# diskohedron4w_revc_termination.net
KiCad netlist of a schematic drawn in EAGLE
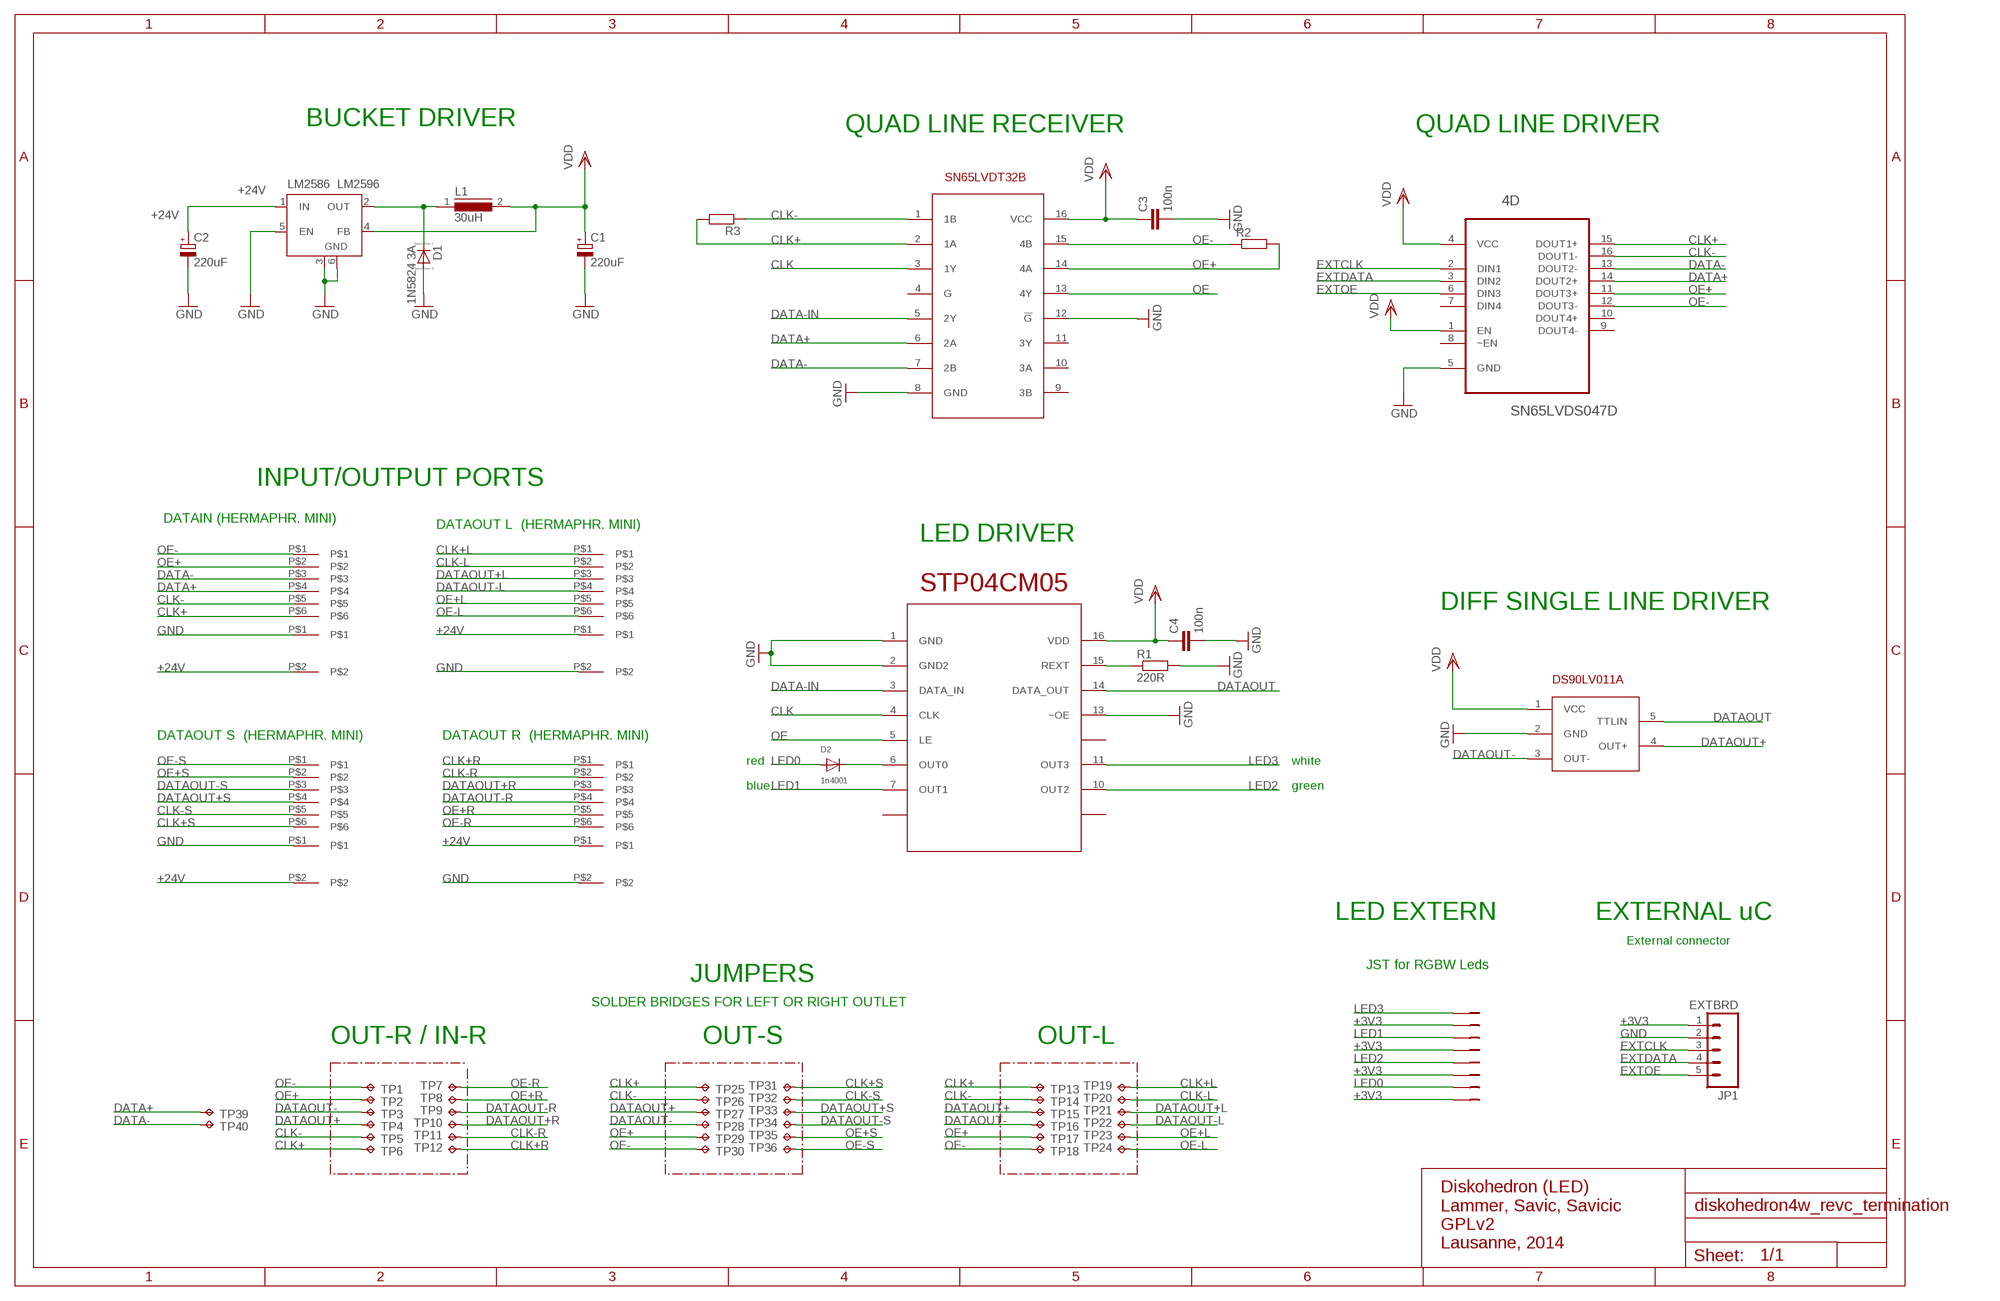
[diagram p0: schematic, sheet 1]

(export (version "E")
  (design (tool "Eeschema 10.0.6"))
  (components
    (comp (ref "1D")
      (value "DS90LV011A")
      (footprint "eagle-import:SOT23-5")
      (libsource (lib "eagle-import") (part "DS90LV011A"))
    )
    (comp (ref "4D")
      (value "SN65LVDS047D")
      (footprint "eagle-import:SOIC127P600X175-16N")
      (libsource (lib "eagle-import") (part "SN65LVDS047D"))
    )
    (comp (ref "4R")
      (value "SN65LVDST32")
      (footprint "eagle-import:SOIC16")
      (libsource (lib "eagle-import") (part "SN65LVDST32"))
    )
    (comp (ref "C1")
      (value "220uF")
      (footprint "eagle-import:175TMP-0810")
      (libsource (lib "eagle-import") (part "CPOL-EU175TMP-0810"))
    )
    (comp (ref "C2")
      (value "220uF")
      (footprint "eagle-import:175TMP-0810")
      (libsource (lib "eagle-import") (part "CPOL-EU175TMP-0810"))
    )
    (comp (ref "C3")
      (value "100n")
      (footprint "eagle-import:C0805")
      (libsource (lib "eagle-import") (part "C-EUC0805"))
    )
    (comp (ref "C4")
      (value "100n")
      (footprint "eagle-import:C0805")
      (libsource (lib "eagle-import") (part "C-EUC0805"))
    )
    (comp (ref "D1")
      (value "1N5824 3A")
      (footprint "eagle-import:DIODE_SMC")
      (libsource (lib "eagle-import") (part "DIODE_E-SMC"))
    )
    (comp (ref "D2")
      (value "1n4001")
      (footprint "eagle-import:SMADIODE")
      (libsource (lib "eagle-import") (part "DIODESMA"))
    )
    (comp (ref "IN1")
      (value "HERMAPHRODITMINI6PIN")
      (footprint "eagle-import:HERMAPHRODITMINI6PIN")
      (libsource (lib "eagle-import") (part "HERMAPHRODITMINI6PIN"))
    )
    (comp (ref "JP1")
      (value "EXTBRD")
      (footprint "eagle-import:1X05")
      (libsource (lib "eagle-import") (part "M05PTH"))
    )
    (comp (ref "JST")
      (value "8PIN-ZH")
      (footprint "eagle-import:B8B-ZH")
      (libsource (lib "eagle-import") (part "8PIN-ZH"))
    )
    (comp (ref "L1")
      (value "30uH")
      (footprint "eagle-import:DR127")
      (libsource (lib "eagle-import") (part "DR127"))
    )
    (comp (ref "LM2586")
      (value "LM2596")
      (footprint "eagle-import:TO263-5")
      (libsource (lib "eagle-import") (part "LM2596S"))
    )
    (comp (ref "OUT-L")
      (value "HERMAPHRODITMINI6PIN")
      (footprint "eagle-import:HERMAPHRODITMINI6PIN")
      (libsource (lib "eagle-import") (part "HERMAPHRODITMINI6PIN"))
    )
    (comp (ref "OUT-R")
      (value "HERMAPHRODITMINI6PIN")
      (footprint "eagle-import:HERMAPHRODITMINI6PIN")
      (libsource (lib "eagle-import") (part "HERMAPHRODITMINI6PIN"))
    )
    (comp (ref "OUT-R1")
      (value "HERMAPHRODITMINI6PIN")
      (footprint "eagle-import:HERMAPHRODITMINI6PIN")
      (libsource (lib "eagle-import") (part "HERMAPHRODITMINI6PIN"))
    )
    (comp (ref "R1")
      (value "220R")
      (footprint "eagle-import:M0805")
      (libsource (lib "eagle-import") (part "resistor_R-EU_M0805"))
    )
    (comp (ref "R2")
      (value "R-EU_R0402")
      (footprint "eagle-import:R0402")
      (libsource (lib "eagle-import") (part "R-EU_R0402"))
    )
    (comp (ref "R3")
      (value "R-EU_R0402")
      (footprint "eagle-import:R0402")
      (libsource (lib "eagle-import") (part "R-EU_R0402"))
    )
    (comp (ref "STP04")
      (value "STP04CM05")
      (footprint "eagle-import:TSSOP16")
      (libsource (lib "eagle-import") (part "STP04CM05"))
    )
    (comp (ref "TP1")
      (value "TPTP12SQ")
      (footprint "eagle-import:TP12SQ")
      (libsource (lib "eagle-import") (part "TPTP12SQ"))
    )
    (comp (ref "TP2")
      (value "TPTP12SQ")
      (footprint "eagle-import:TP12SQ")
      (libsource (lib "eagle-import") (part "TPTP12SQ"))
    )
    (comp (ref "TP3")
      (value "TPTP09SQ")
      (footprint "eagle-import:TP09SQ")
      (libsource (lib "eagle-import") (part "TPTP09SQ"))
    )
    (comp (ref "TP4")
      (value "TPTP09SQ")
      (footprint "eagle-import:TP09SQ")
      (libsource (lib "eagle-import") (part "TPTP09SQ"))
    )
    (comp (ref "TP5")
      (value "TPTP12SQ")
      (footprint "eagle-import:TP12SQ")
      (libsource (lib "eagle-import") (part "TPTP12SQ"))
    )
    (comp (ref "TP6")
      (value "TPTP12SQ")
      (footprint "eagle-import:TP12SQ")
      (libsource (lib "eagle-import") (part "TPTP12SQ"))
    )
    (comp (ref "TP7")
      (value "TPTP12SQ")
      (footprint "eagle-import:TP12SQ")
      (libsource (lib "eagle-import") (part "TPTP12SQ"))
    )
    (comp (ref "TP8")
      (value "TPTP12SQ")
      (footprint "eagle-import:TP12SQ")
      (libsource (lib "eagle-import") (part "TPTP12SQ"))
    )
    (comp (ref "TP9")
      (value "TPTP20SQ")
      (footprint "eagle-import:TP20SQ")
      (libsource (lib "eagle-import") (part "TPTP20SQ"))
    )
    (comp (ref "TP10")
      (value "TPTP20SQ")
      (footprint "eagle-import:TP20SQ")
      (libsource (lib "eagle-import") (part "TPTP20SQ"))
    )
    (comp (ref "TP11")
      (value "TPTP12SQ")
      (footprint "eagle-import:TP12SQ")
      (libsource (lib "eagle-import") (part "TPTP12SQ"))
    )
    (comp (ref "TP12")
      (value "TPTP12SQ")
      (footprint "eagle-import:TP12SQ")
      (libsource (lib "eagle-import") (part "TPTP12SQ"))
    )
    (comp (ref "TP13")
      (value "TPTP12SQ")
      (footprint "eagle-import:TP12SQ")
      (libsource (lib "eagle-import") (part "TPTP12SQ"))
    )
    (comp (ref "TP14")
      (value "TPTP12SQ")
      (footprint "eagle-import:TP12SQ")
      (libsource (lib "eagle-import") (part "TPTP12SQ"))
    )
    (comp (ref "TP15")
      (value "TPTP12SQ")
      (footprint "eagle-import:TP12SQ")
      (libsource (lib "eagle-import") (part "TPTP12SQ"))
    )
    (comp (ref "TP16")
      (value "TPTP12SQ")
      (footprint "eagle-import:TP12SQ")
      (libsource (lib "eagle-import") (part "TPTP12SQ"))
    )
    (comp (ref "TP17")
      (value "TPTP12SQ")
      (footprint "eagle-import:TP12SQ")
      (libsource (lib "eagle-import") (part "TPTP12SQ"))
    )
    (comp (ref "TP18")
      (value "TPTP12SQ")
      (footprint "eagle-import:TP12SQ")
      (libsource (lib "eagle-import") (part "TPTP12SQ"))
    )
    (comp (ref "TP19")
      (value "TPTP12SQ")
      (footprint "eagle-import:TP12SQ")
      (libsource (lib "eagle-import") (part "TPTP12SQ"))
    )
    (comp (ref "TP20")
      (value "TPTP12SQ")
      (footprint "eagle-import:TP12SQ")
      (libsource (lib "eagle-import") (part "TPTP12SQ"))
    )
    (comp (ref "TP21")
      (value "TPTP12SQ")
      (footprint "eagle-import:TP12SQ")
      (libsource (lib "eagle-import") (part "TPTP12SQ"))
    )
    (comp (ref "TP22")
      (value "TPTP12SQ")
      (footprint "eagle-import:TP12SQ")
      (libsource (lib "eagle-import") (part "TPTP12SQ"))
    )
    (comp (ref "TP23")
      (value "TPTP12SQ")
      (footprint "eagle-import:TP12SQ")
      (libsource (lib "eagle-import") (part "TPTP12SQ"))
    )
    (comp (ref "TP24")
      (value "TPTP12SQ")
      (footprint "eagle-import:TP12SQ")
      (libsource (lib "eagle-import") (part "TPTP12SQ"))
    )
    (comp (ref "TP25")
      (value "TPTP12SQ")
      (footprint "eagle-import:TP12SQ")
      (libsource (lib "eagle-import") (part "TPTP12SQ"))
    )
    (comp (ref "TP26")
      (value "TPTP12SQ")
      (footprint "eagle-import:TP12SQ")
      (libsource (lib "eagle-import") (part "TPTP12SQ"))
    )
    (comp (ref "TP27")
      (value "TPTP12SQ")
      (footprint "eagle-import:TP12SQ")
      (libsource (lib "eagle-import") (part "TPTP12SQ"))
    )
    (comp (ref "TP28")
      (value "TPTP12SQ")
      (footprint "eagle-import:TP12SQ")
      (libsource (lib "eagle-import") (part "TPTP12SQ"))
    )
    (comp (ref "TP29")
      (value "TPTP12SQ")
      (footprint "eagle-import:TP12SQ")
      (libsource (lib "eagle-import") (part "TPTP12SQ"))
    )
    (comp (ref "TP30")
      (value "TPTP12SQ")
      (footprint "eagle-import:TP12SQ")
      (libsource (lib "eagle-import") (part "TPTP12SQ"))
    )
    (comp (ref "TP31")
      (value "TPTP12SQ")
      (footprint "eagle-import:TP12SQ")
      (libsource (lib "eagle-import") (part "TPTP12SQ"))
    )
    (comp (ref "TP32")
      (value "TPTP12SQ")
      (footprint "eagle-import:TP12SQ")
      (libsource (lib "eagle-import") (part "TPTP12SQ"))
    )
    (comp (ref "TP33")
      (value "TPTP12SQ")
      (footprint "eagle-import:TP12SQ")
      (libsource (lib "eagle-import") (part "TPTP12SQ"))
    )
    (comp (ref "TP34")
      (value "TPTP12SQ")
      (footprint "eagle-import:TP12SQ")
      (libsource (lib "eagle-import") (part "TPTP12SQ"))
    )
    (comp (ref "TP35")
      (value "TPTP12SQ")
      (footprint "eagle-import:TP12SQ")
      (libsource (lib "eagle-import") (part "TPTP12SQ"))
    )
    (comp (ref "TP36")
      (value "TPTP12SQ")
      (footprint "eagle-import:TP12SQ")
      (libsource (lib "eagle-import") (part "TPTP12SQ"))
    )
    (comp (ref "TP39")
      (value "TPTP09SQ")
      (footprint "eagle-import:TP09SQ")
      (libsource (lib "eagle-import") (part "TPTP09SQ"))
    )
    (comp (ref "TP40")
      (value "TPTP09SQ")
      (footprint "eagle-import:TP09SQ")
      (libsource (lib "eagle-import") (part "TPTP09SQ"))
    )
    (comp (ref "U$1")
      (value "HERMAPHRODIT2PIN")
      (footprint "eagle-import:HERMAPHRODIT2PIN")
      (libsource (lib "eagle-import") (part "HERMAPHRODIT2PIN"))
    )
    (comp (ref "U$6")
      (value "HERMAPHRODIT2PIN")
      (footprint "eagle-import:HERMAPHRODIT2PIN")
      (libsource (lib "eagle-import") (part "HERMAPHRODIT2PIN"))
    )
    (comp (ref "U$7")
      (value "HERMAPHRODIT2PIN")
      (footprint "eagle-import:HERMAPHRODIT2PIN")
      (libsource (lib "eagle-import") (part "HERMAPHRODIT2PIN"))
    )
    (comp (ref "U$12")
      (value "HERMAPHRODIT2PIN")
      (footprint "eagle-import:HERMAPHRODIT2PIN")
      (libsource (lib "eagle-import") (part "HERMAPHRODIT2PIN"))
    )
  )
  (nets
    (net (code "1") (name "/+24V") (class "Default")
      (node (ref "C2") (pin "+") (pinfunction "+_+") (pintype "passive"))
      (node (ref "LM2586") (pin "1") (pinfunction "IN_1") (pintype "input"))
      (node (ref "U$1") (pin "P$2") (pinfunction "P$2_P$2") (pintype "bidirectional"))
      (node (ref "U$12") (pin "P$1") (pinfunction "P$1_P$1") (pintype "bidirectional"))
      (node (ref "U$6") (pin "P$1") (pinfunction "P$1_P$1") (pintype "bidirectional"))
      (node (ref "U$7") (pin "P$2") (pinfunction "P$2_P$2") (pintype "bidirectional"))
    )
    (net (code "2") (name "/CLK") (class "Default")
      (node (ref "4R") (pin "3") (pinfunction "1Y_3") (pintype "bidirectional"))
      (node (ref "STP04") (pin "4") (pinfunction "CLK_4") (pintype "bidirectional"))
    )
    (net (code "3") (name "/CLK+") (class "Default")
      (node (ref "4D") (pin "15") (pinfunction "DOUT1+_15") (pintype "output"))
      (node (ref "4R") (pin "2") (pinfunction "1A_2") (pintype "bidirectional"))
      (node (ref "IN1") (pin "P$6") (pinfunction "P$6_P$6") (pintype "bidirectional"))
      (node (ref "R3") (pin "2") (pinfunction "2_2") (pintype "passive"))
      (node (ref "TP13") (pin "TP") (pinfunction "TP_TP") (pintype "input"))
      (node (ref "TP25") (pin "TP") (pinfunction "TP_TP") (pintype "input"))
      (node (ref "TP6") (pin "TP") (pinfunction "TP_TP") (pintype "input"))
    )
    (net (code "4") (name "/CLK+L") (class "Default")
      (node (ref "OUT-L") (pin "P$1") (pinfunction "P$1_P$1") (pintype "bidirectional"))
      (node (ref "TP19") (pin "TP") (pinfunction "TP_TP") (pintype "input"))
    )
    (net (code "5") (name "/CLK+R") (class "Default")
      (node (ref "OUT-R") (pin "P$1") (pinfunction "P$1_P$1") (pintype "bidirectional"))
      (node (ref "TP12") (pin "TP") (pinfunction "TP_TP") (pintype "input"))
    )
    (net (code "6") (name "/CLK+S") (class "Default")
      (node (ref "OUT-R1") (pin "P$6") (pinfunction "P$6_P$6") (pintype "bidirectional"))
      (node (ref "TP31") (pin "TP") (pinfunction "TP_TP") (pintype "input"))
    )
    (net (code "7") (name "/CLK-") (class "Default")
      (node (ref "4D") (pin "16") (pinfunction "DOUT1-_16") (pintype "output"))
      (node (ref "4R") (pin "1") (pinfunction "1B_1") (pintype "bidirectional"))
      (node (ref "IN1") (pin "P$5") (pinfunction "P$5_P$5") (pintype "bidirectional"))
      (node (ref "R3") (pin "1") (pinfunction "1_1") (pintype "passive"))
      (node (ref "TP14") (pin "TP") (pinfunction "TP_TP") (pintype "input"))
      (node (ref "TP26") (pin "TP") (pinfunction "TP_TP") (pintype "input"))
      (node (ref "TP5") (pin "TP") (pinfunction "TP_TP") (pintype "input"))
    )
    (net (code "8") (name "/CLK-L") (class "Default")
      (node (ref "OUT-L") (pin "P$2") (pinfunction "P$2_P$2") (pintype "bidirectional"))
      (node (ref "TP20") (pin "TP") (pinfunction "TP_TP") (pintype "input"))
    )
    (net (code "9") (name "/CLK-R") (class "Default")
      (node (ref "OUT-R") (pin "P$2") (pinfunction "P$2_P$2") (pintype "bidirectional"))
      (node (ref "TP11") (pin "TP") (pinfunction "TP_TP") (pintype "input"))
    )
    (net (code "10") (name "/CLK-S") (class "Default")
      (node (ref "OUT-R1") (pin "P$5") (pinfunction "P$5_P$5") (pintype "bidirectional"))
      (node (ref "TP32") (pin "TP") (pinfunction "TP_TP") (pintype "input"))
    )
    (net (code "11") (name "/DATA+") (class "Default")
      (node (ref "4D") (pin "14") (pinfunction "DOUT2+_14") (pintype "output"))
      (node (ref "4R") (pin "6") (pinfunction "2A_6") (pintype "bidirectional"))
      (node (ref "IN1") (pin "P$4") (pinfunction "P$4_P$4") (pintype "bidirectional"))
      (node (ref "TP39") (pin "TP") (pinfunction "TP_TP") (pintype "input"))
    )
    (net (code "12") (name "/DATA-") (class "Default")
      (node (ref "4D") (pin "13") (pinfunction "DOUT2-_13") (pintype "output"))
      (node (ref "4R") (pin "7") (pinfunction "2B_7") (pintype "bidirectional"))
      (node (ref "IN1") (pin "P$3") (pinfunction "P$3_P$3") (pintype "bidirectional"))
      (node (ref "TP40") (pin "TP") (pinfunction "TP_TP") (pintype "input"))
    )
    (net (code "13") (name "/DATA-IN") (class "Default")
      (node (ref "4R") (pin "5") (pinfunction "2Y_5") (pintype "bidirectional"))
      (node (ref "STP04") (pin "3") (pinfunction "DATA_IN_3") (pintype "bidirectional"))
    )
    (net (code "14") (name "/DATAOUT") (class "Default")
      (node (ref "1D") (pin "5") (pinfunction "TTLIN_5") (pintype "bidirectional"))
      (node (ref "STP04") (pin "14") (pinfunction "DATA_OUT_14") (pintype "bidirectional"))
    )
    (net (code "15") (name "/DATAOUT+") (class "Default")
      (node (ref "1D") (pin "4") (pinfunction "OUT+_4") (pintype "bidirectional"))
      (node (ref "TP15") (pin "TP") (pinfunction "TP_TP") (pintype "input"))
      (node (ref "TP27") (pin "TP") (pinfunction "TP_TP") (pintype "input"))
      (node (ref "TP4") (pin "TP") (pinfunction "TP_TP") (pintype "input"))
    )
    (net (code "16") (name "/DATAOUT+L") (class "Default")
      (node (ref "OUT-L") (pin "P$3") (pinfunction "P$3_P$3") (pintype "bidirectional"))
      (node (ref "TP21") (pin "TP") (pinfunction "TP_TP") (pintype "input"))
    )
    (net (code "17") (name "/DATAOUT+R") (class "Default")
      (node (ref "OUT-R") (pin "P$3") (pinfunction "P$3_P$3") (pintype "bidirectional"))
      (node (ref "TP10") (pin "TP") (pinfunction "TP_TP") (pintype "input"))
    )
    (net (code "18") (name "/DATAOUT+S") (class "Default")
      (node (ref "OUT-R1") (pin "P$4") (pinfunction "P$4_P$4") (pintype "bidirectional"))
      (node (ref "TP33") (pin "TP") (pinfunction "TP_TP") (pintype "input"))
    )
    (net (code "19") (name "/DATAOUT-") (class "Default")
      (node (ref "1D") (pin "3") (pinfunction "OUT-_3") (pintype "bidirectional"))
      (node (ref "TP16") (pin "TP") (pinfunction "TP_TP") (pintype "input"))
      (node (ref "TP28") (pin "TP") (pinfunction "TP_TP") (pintype "input"))
      (node (ref "TP3") (pin "TP") (pinfunction "TP_TP") (pintype "input"))
    )
    (net (code "20") (name "/DATAOUT-L") (class "Default")
      (node (ref "OUT-L") (pin "P$4") (pinfunction "P$4_P$4") (pintype "bidirectional"))
      (node (ref "TP22") (pin "TP") (pinfunction "TP_TP") (pintype "input"))
    )
    (net (code "21") (name "/DATAOUT-R") (class "Default")
      (node (ref "OUT-R") (pin "P$4") (pinfunction "P$4_P$4") (pintype "bidirectional"))
      (node (ref "TP9") (pin "TP") (pinfunction "TP_TP") (pintype "input"))
    )
    (net (code "22") (name "/DATAOUT-S") (class "Default")
      (node (ref "OUT-R1") (pin "P$3") (pinfunction "P$3_P$3") (pintype "bidirectional"))
      (node (ref "TP34") (pin "TP") (pinfunction "TP_TP") (pintype "input"))
    )
    (net (code "23") (name "/EXTCLK") (class "Default")
      (node (ref "4D") (pin "2") (pinfunction "DIN1_2") (pintype "input"))
      (node (ref "JP1") (pin "3") (pinfunction "3_3") (pintype "passive"))
    )
    (net (code "24") (name "/EXTDATA") (class "Default")
      (node (ref "4D") (pin "3") (pinfunction "DIN2_3") (pintype "input"))
      (node (ref "JP1") (pin "4") (pinfunction "4_4") (pintype "passive"))
    )
    (net (code "25") (name "/EXTOE") (class "Default")
      (node (ref "4D") (pin "6") (pinfunction "DIN3_6") (pintype "input"))
      (node (ref "JP1") (pin "5") (pinfunction "5_5") (pintype "passive"))
    )
    (net (code "26") (name "/LED0") (class "Default")
      (node (ref "D2") (pin "A") (pinfunction "A_A") (pintype "passive"))
      (node (ref "JST") (pin "7") (pinfunction "1_7") (pintype "passive"))
    )
    (net (code "27") (name "/LED1") (class "Default")
      (node (ref "JST") (pin "3") (pinfunction "1_3") (pintype "passive"))
      (node (ref "STP04") (pin "7") (pinfunction "OUT1_7") (pintype "bidirectional"))
    )
    (net (code "28") (name "/LED2") (class "Default")
      (node (ref "JST") (pin "5") (pinfunction "1_5") (pintype "passive"))
      (node (ref "STP04") (pin "10") (pinfunction "OUT2_10") (pintype "bidirectional"))
    )
    (net (code "29") (name "/LED3") (class "Default")
      (node (ref "JST") (pin "1") (pinfunction "1_1") (pintype "passive"))
      (node (ref "STP04") (pin "11") (pinfunction "OUT3_11") (pintype "bidirectional"))
    )
    (net (code "30") (name "/OE") (class "Default")
      (node (ref "4R") (pin "13") (pinfunction "4Y_13") (pintype "bidirectional"))
      (node (ref "STP04") (pin "5") (pinfunction "LE_5") (pintype "bidirectional"))
    )
    (net (code "31") (name "/OE+") (class "Default")
      (node (ref "4D") (pin "11") (pinfunction "DOUT3+_11") (pintype "output"))
      (node (ref "4R") (pin "14") (pinfunction "4A_14") (pintype "bidirectional"))
      (node (ref "IN1") (pin "P$2") (pinfunction "P$2_P$2") (pintype "bidirectional"))
      (node (ref "R2") (pin "2") (pinfunction "2_2") (pintype "passive"))
      (node (ref "TP17") (pin "TP") (pinfunction "TP_TP") (pintype "input"))
      (node (ref "TP2") (pin "TP") (pinfunction "TP_TP") (pintype "input"))
      (node (ref "TP29") (pin "TP") (pinfunction "TP_TP") (pintype "input"))
    )
    (net (code "32") (name "/OE+L") (class "Default")
      (node (ref "OUT-L") (pin "P$5") (pinfunction "P$5_P$5") (pintype "bidirectional"))
      (node (ref "TP23") (pin "TP") (pinfunction "TP_TP") (pintype "input"))
    )
    (net (code "33") (name "/OE+R") (class "Default")
      (node (ref "OUT-R") (pin "P$5") (pinfunction "P$5_P$5") (pintype "bidirectional"))
      (node (ref "TP8") (pin "TP") (pinfunction "TP_TP") (pintype "input"))
    )
    (net (code "34") (name "/OE+S") (class "Default")
      (node (ref "OUT-R1") (pin "P$2") (pinfunction "P$2_P$2") (pintype "bidirectional"))
      (node (ref "TP35") (pin "TP") (pinfunction "TP_TP") (pintype "input"))
    )
    (net (code "35") (name "/OE-") (class "Default")
      (node (ref "4D") (pin "12") (pinfunction "DOUT3-_12") (pintype "output"))
      (node (ref "4R") (pin "15") (pinfunction "4B_15") (pintype "bidirectional"))
      (node (ref "IN1") (pin "P$1") (pinfunction "P$1_P$1") (pintype "bidirectional"))
      (node (ref "R2") (pin "1") (pinfunction "1_1") (pintype "passive"))
      (node (ref "TP1") (pin "TP") (pinfunction "TP_TP") (pintype "input"))
      (node (ref "TP18") (pin "TP") (pinfunction "TP_TP") (pintype "input"))
      (node (ref "TP30") (pin "TP") (pinfunction "TP_TP") (pintype "input"))
    )
    (net (code "36") (name "/OE-L") (class "Default")
      (node (ref "OUT-L") (pin "P$6") (pinfunction "P$6_P$6") (pintype "bidirectional"))
      (node (ref "TP24") (pin "TP") (pinfunction "TP_TP") (pintype "input"))
    )
    (net (code "37") (name "/OE-R") (class "Default")
      (node (ref "OUT-R") (pin "P$6") (pinfunction "P$6_P$6") (pintype "bidirectional"))
      (node (ref "TP7") (pin "TP") (pinfunction "TP_TP") (pintype "input"))
    )
    (net (code "38") (name "/OE-S") (class "Default")
      (node (ref "OUT-R1") (pin "P$1") (pinfunction "P$1_P$1") (pintype "bidirectional"))
      (node (ref "TP36") (pin "TP") (pinfunction "TP_TP") (pintype "input"))
    )
    (net (code "39") (name "GND") (class "Default")
      (node (ref "1D") (pin "2") (pinfunction "GND_2") (pintype "bidirectional"))
      (node (ref "4D") (pin "5") (pinfunction "GND_5") (pintype "passive"))
      (node (ref "4R") (pin "12") (pinfunction "~{G}_12") (pintype "bidirectional"))
      (node (ref "4R") (pin "8") (pinfunction "GND_8") (pintype "bidirectional"))
      (node (ref "C1") (pin "-") (pinfunction "-_-") (pintype "passive"))
      (node (ref "C2") (pin "-") (pinfunction "-_-") (pintype "passive"))
      (node (ref "C3") (pin "2") (pinfunction "2_2") (pintype "passive"))
      (node (ref "C4") (pin "2") (pinfunction "2_2") (pintype "passive"))
      (node (ref "D1") (pin "A") (pinfunction "C_A") (pintype "passive"))
      (node (ref "JP1") (pin "2") (pinfunction "2_2") (pintype "passive"))
      (node (ref "LM2586") (pin "3") (pinfunction "GND_3") (pintype "power_in"))
      (node (ref "LM2586") (pin "5") (pinfunction "EN_5") (pintype "input"))
      (node (ref "LM2586") (pin "6") (pinfunction "GND_6") (pintype "power_in"))
      (node (ref "R1") (pin "2") (pinfunction "2_2") (pintype "passive"))
      (node (ref "STP04") (pin "1") (pinfunction "GND_1") (pintype "bidirectional"))
      (node (ref "STP04") (pin "13") (pinfunction "~{OE}_13") (pintype "bidirectional"))
      (node (ref "STP04") (pin "2") (pinfunction "GND2_2") (pintype "bidirectional"))
      (node (ref "U$1") (pin "P$1") (pinfunction "P$1_P$1") (pintype "bidirectional"))
      (node (ref "U$12") (pin "P$2") (pinfunction "P$2_P$2") (pintype "bidirectional"))
      (node (ref "U$6") (pin "P$2") (pinfunction "P$2_P$2") (pintype "bidirectional"))
      (node (ref "U$7") (pin "P$1") (pinfunction "P$1_P$1") (pintype "bidirectional"))
    )
    (net (code "40") (name "Net-(D1-A)") (class "Default")
      (node (ref "D1") (pin "C") (pinfunction "A_C") (pintype "passive"))
      (node (ref "L1") (pin "1") (pinfunction "1_1") (pintype "passive"))
      (node (ref "LM2586") (pin "2") (pinfunction "OUT_2") (pintype "output"))
    )
    (net (code "41") (name "Net-(STP04-OUT0)") (class "Default")
      (node (ref "D2") (pin "C") (pinfunction "C_C") (pintype "passive"))
      (node (ref "STP04") (pin "6") (pinfunction "OUT0_6") (pintype "bidirectional"))
    )
    (net (code "42") (name "Net-(STP04-REXT)") (class "Default")
      (node (ref "R1") (pin "1") (pinfunction "1_1") (pintype "passive"))
      (node (ref "STP04") (pin "15") (pinfunction "REXT_15") (pintype "bidirectional"))
    )
    (net (code "43") (name "VDD") (class "Default")
      (node (ref "1D") (pin "1") (pinfunction "VCC_1") (pintype "bidirectional"))
      (node (ref "4D") (pin "1") (pinfunction "EN_1") (pintype "input"))
      (node (ref "4D") (pin "4") (pinfunction "VCC_4") (pintype "power_in"))
      (node (ref "4R") (pin "16") (pinfunction "VCC_16") (pintype "bidirectional"))
      (node (ref "C1") (pin "+") (pinfunction "+_+") (pintype "passive"))
      (node (ref "C3") (pin "1") (pinfunction "1_1") (pintype "passive"))
      (node (ref "C4") (pin "1") (pinfunction "1_1") (pintype "passive"))
      (node (ref "JP1") (pin "1") (pinfunction "1_1") (pintype "passive"))
      (node (ref "JST") (pin "2") (pinfunction "1_2") (pintype "passive"))
      (node (ref "JST") (pin "4") (pinfunction "1_4") (pintype "passive"))
      (node (ref "JST") (pin "6") (pinfunction "1_6") (pintype "passive"))
      (node (ref "JST") (pin "8") (pinfunction "1_8") (pintype "passive"))
      (node (ref "L1") (pin "2") (pinfunction "2_2") (pintype "passive"))
      (node (ref "LM2586") (pin "4") (pinfunction "FB_4") (pintype "input"))
      (node (ref "STP04") (pin "16") (pinfunction "VDD_16") (pintype "bidirectional"))
    )
    (net (code "44") (name "unconnected-(4D-DIN4-Pad7)") (class "Default")
      (node (ref "4D") (pin "7") (pinfunction "DIN4_7") (pintype "input"))
    )
    (net (code "45") (name "unconnected-(4D-DOUT4+-Pad10)") (class "Default")
      (node (ref "4D") (pin "10") (pinfunction "DOUT4+_10") (pintype "output"))
    )
    (net (code "46") (name "unconnected-(4D-DOUT4--Pad9)") (class "Default")
      (node (ref "4D") (pin "9") (pinfunction "DOUT4-_9") (pintype "output"))
    )
    (net (code "47") (name "unconnected-(4D-~{EN}-Pad8)") (class "Default")
      (node (ref "4D") (pin "8") (pinfunction "~{EN}_8") (pintype "input"))
    )
    (net (code "48") (name "unconnected-(4R-3A-Pad10)") (class "Default")
      (node (ref "4R") (pin "10") (pinfunction "3A_10") (pintype "bidirectional"))
    )
    (net (code "49") (name "unconnected-(4R-3B-Pad9)") (class "Default")
      (node (ref "4R") (pin "9") (pinfunction "3B_9") (pintype "bidirectional"))
    )
    (net (code "50") (name "unconnected-(4R-3Y-Pad11)") (class "Default")
      (node (ref "4R") (pin "11") (pinfunction "3Y_11") (pintype "bidirectional"))
    )
    (net (code "51") (name "unconnected-(4R-G-Pad4)") (class "Default")
      (node (ref "4R") (pin "4") (pinfunction "G_4") (pintype "bidirectional"))
    )
    (net (code "52") (name "unconnected-(STP04-N.C1-Pad8)") (class "Default")
      (node (ref "STP04") (pin "8") (pinfunction "N.C1_8") (pintype "bidirectional"))
    )
    (net (code "53") (name "unconnected-(STP04-NC-Pad9)") (class "Default")
      (node (ref "STP04") (pin "9") (pinfunction "NC_9") (pintype "bidirectional"))
    )
    (net (code "54") (name "unconnected-(STP04-NC3-Pad12)") (class "Default")
      (node (ref "STP04") (pin "12") (pinfunction "NC3_12") (pintype "bidirectional"))
    )
  )
)
